# dac-ic.net
KiCad netlist of a schematic drawn in Altium Designer
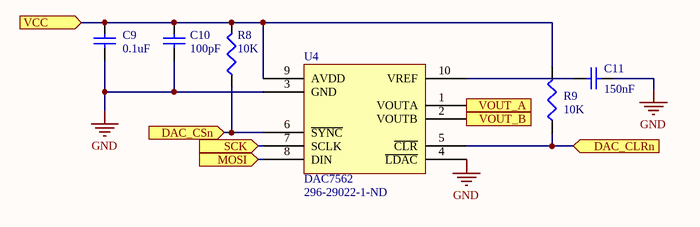
[diagram p0: dac-ic.SchDoc]

(export (version "E")
  (design (tool "Eeschema 10.0.6"))
  (components
    (comp (ref "C9")
      (value "0.1uF")
      (footprint "0402")
      (description "Capacitor (Semiconductor SIM Model)")
      (fields (field (name "PUBLISHER") "Altium Limited"))
      (libsource (lib "Miscellaneous Devices") (part "Cap Semi"))
    )
    (comp (ref "C10")
      (value "100pF")
      (footprint "0402")
      (description "Capacitor (Semiconductor SIM Model)")
      (fields (field (name "PUBLISHER") "Altium Limited"))
      (libsource (lib "Miscellaneous Devices") (part "Cap Semi"))
    )
    (comp (ref "C11")
      (value "150nF")
      (footprint "0402")
      (description "Capacitor (Semiconductor SIM Model)")
      (fields (field (name "PUBLISHER") "Altium Limited"))
      (libsource (lib "Miscellaneous Devices") (part "Cap Semi"))
    )
    (comp (ref "R8")
      (value "10K")
      (footprint "0402")
      (description "Resistor")
      (fields (field (name "PUBLISHER") "Altium Limited"))
      (libsource (lib "Miscellaneous Devices") (part "Res3"))
    )
    (comp (ref "R9")
      (value "10K")
      (footprint "0402")
      (description "Resistor")
      (fields (field (name "PUBLISHER") "Altium Limited"))
      (libsource (lib "Miscellaneous Devices") (part "Res3"))
    )
    (comp (ref "U4")
      (value "DAC7562")
      (footprint "SOP10-50P300X300-10N")
      (description "12-bit, low-power, voltage-output DAC with internal reference.")
      (fields (field (name "SUPPLIER PART NUMBER 1") "296-29022-1-ND"))
      (libsource (lib "PAY") (part "DAC7562"))
    )
  )
  (nets
    (net (code "1") (name "/DAC_CLRn") (class "Default")
      (node (ref "R9") (pin "1") (pinfunction "1_1") (pintype "passive"))
      (node (ref "U4") (pin "5") (pinfunction "~{CLR}_5") (pintype "passive"))
    )
    (net (code "2") (name "/DAC_CSn") (class "Default")
      (node (ref "R8") (pin "1") (pinfunction "1_1") (pintype "passive"))
      (node (ref "U4") (pin "6") (pinfunction "~{SYNC}_6") (pintype "passive"))
    )
    (net (code "3") (name "/MOSI") (class "Default")
      (node (ref "U4") (pin "8") (pinfunction "DIN_8") (pintype "passive"))
    )
    (net (code "4") (name "/SCK") (class "Default")
      (node (ref "U4") (pin "7") (pinfunction "SCLK_7") (pintype "passive"))
    )
    (net (code "5") (name "/VCC") (class "Default")
      (node (ref "C10") (pin "2") (pinfunction "2_2") (pintype "passive"))
      (node (ref "C9") (pin "2") (pinfunction "2_2") (pintype "passive"))
      (node (ref "R8") (pin "2") (pinfunction "2_2") (pintype "passive"))
      (node (ref "R9") (pin "2") (pinfunction "2_2") (pintype "passive"))
      (node (ref "U4") (pin "9") (pinfunction "AVDD_9") (pintype "passive"))
    )
    (net (code "6") (name "/VOUT_A") (class "Default")
      (node (ref "U4") (pin "1") (pinfunction "VOUTA_1") (pintype "passive"))
    )
    (net (code "7") (name "/VOUT_B") (class "Default")
      (node (ref "U4") (pin "2") (pinfunction "VOUTB_2") (pintype "passive"))
    )
    (net (code "8") (name "GND") (class "Default")
      (node (ref "C10") (pin "1") (pinfunction "1_1") (pintype "passive"))
      (node (ref "C11") (pin "2") (pinfunction "2_2") (pintype "passive"))
      (node (ref "C9") (pin "1") (pinfunction "1_1") (pintype "passive"))
      (node (ref "U4") (pin "3") (pinfunction "GND_3") (pintype "passive"))
      (node (ref "U4") (pin "4") (pinfunction "~{LDAC}_4") (pintype "passive"))
    )
    (net (code "9") (name "Net-(U4-VREF)") (class "Default")
      (node (ref "C11") (pin "1") (pinfunction "1_1") (pintype "passive"))
      (node (ref "U4") (pin "10") (pinfunction "VREF_10") (pintype "passive"))
    )
  )
)
